# lunchbeats_-_amp.net
KiCad netlist of a schematic drawn in EAGLE
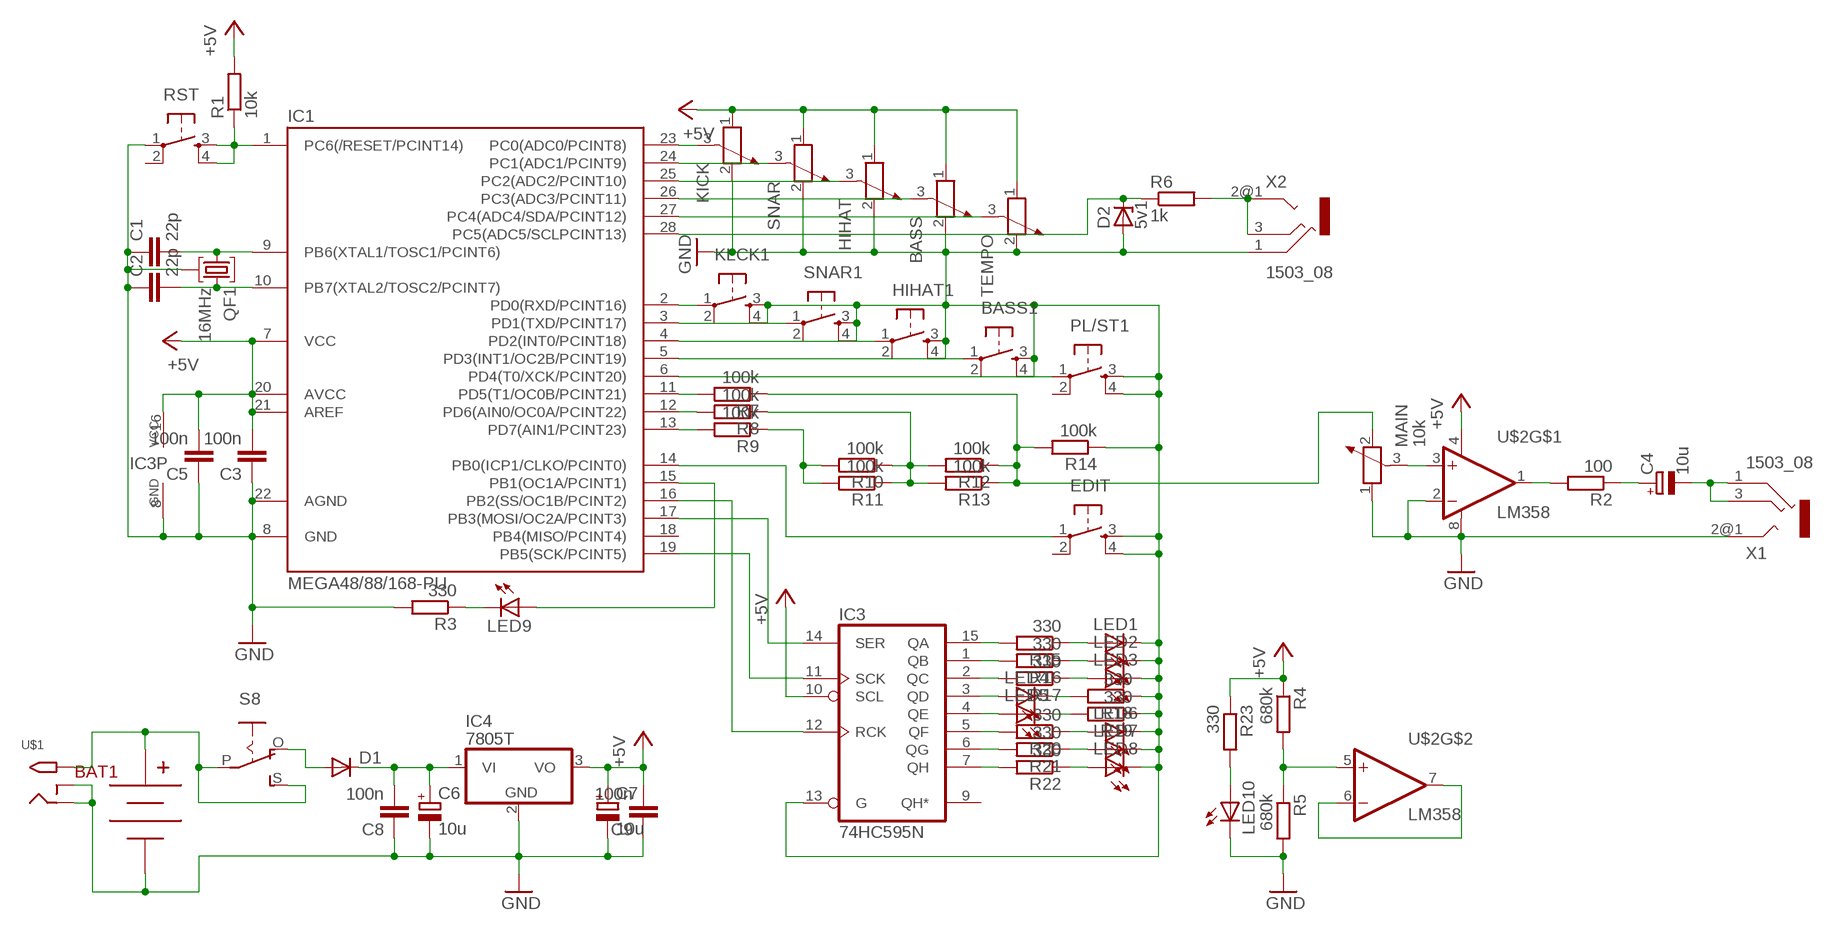
[diagram p0: schematic, sheet 1]

(export (version "E")
  (design (tool "Eeschema 10.0.6"))
  (components
    (comp (ref "BASS")
      (value "POTENTIOMETER_PT-10")
      (footprint "eagle-import:PT-10")
      (libsource (lib "eagle-import") (part "POTENTIOMETER_PT-10"))
    )
    (comp (ref "BASS1")
      (value "TAC_SWITCHPTH")
      (footprint "eagle-import:TACTILE-PTH")
      (libsource (lib "eagle-import") (part "TAC_SWITCHPTH"))
    )
    (comp (ref "BAT1")
      (value "BC9VPC")
      (footprint "eagle-import:BC9VPC")
      (libsource (lib "eagle-import") (part "BC9VPC"))
    )
    (comp (ref "C1")
      (value "22p")
      (footprint "eagle-import:C025-025X050")
      (libsource (lib "eagle-import") (part "C-EU025-025X050"))
    )
    (comp (ref "C2")
      (value "22p")
      (footprint "eagle-import:C025-025X050")
      (libsource (lib "eagle-import") (part "C-EU025-025X050"))
    )
    (comp (ref "C3")
      (value "100n")
      (footprint "eagle-import:C025-025X050")
      (libsource (lib "eagle-import") (part "C-EU025-025X050"))
    )
    (comp (ref "C4")
      (value "10u")
      (footprint "eagle-import:E2,5-6")
      (libsource (lib "eagle-import") (part "CPOL-EUE2.5-6"))
    )
    (comp (ref "C5")
      (value "100n")
      (footprint "eagle-import:C025-025X050")
      (libsource (lib "eagle-import") (part "C-EU025-025X050"))
    )
    (comp (ref "C6")
      (value "10u")
      (footprint "eagle-import:E2,5-5")
      (libsource (lib "eagle-import") (part "CPOL-EUE2.5-5"))
    )
    (comp (ref "C7")
      (value "10u")
      (footprint "eagle-import:E2,5-5")
      (libsource (lib "eagle-import") (part "CPOL-EUE2.5-5"))
    )
    (comp (ref "C8")
      (value "100n")
      (footprint "eagle-import:C025-025X050")
      (libsource (lib "eagle-import") (part "C-EU025-025X050"))
    )
    (comp (ref "C9")
      (value "100n")
      (footprint "eagle-import:C025-025X050")
      (libsource (lib "eagle-import") (part "C-EU025-025X050"))
    )
    (comp (ref "D1")
      (value "DIODE-D-5")
      (footprint "eagle-import:D-5")
      (libsource (lib "eagle-import") (part "DIODE-D-5"))
    )
    (comp (ref "D2")
      (value "5v1")
      (footprint "eagle-import:ZDIO-2.5")
      (libsource (lib "eagle-import") (part "ZENER-DIODEZD-2.5"))
    )
    (comp (ref "EDIT")
      (value "TAC_SWITCHPTH")
      (footprint "eagle-import:TACTILE-PTH")
      (libsource (lib "eagle-import") (part "TAC_SWITCHPTH"))
    )
    (comp (ref "HIHAT")
      (value "POTENTIOMETER_PT-10")
      (footprint "eagle-import:PT-10")
      (libsource (lib "eagle-import") (part "POTENTIOMETER_PT-10"))
    )
    (comp (ref "HIHAT1")
      (value "TAC_SWITCHPTH")
      (footprint "eagle-import:TACTILE-PTH")
      (libsource (lib "eagle-import") (part "TAC_SWITCHPTH"))
    )
    (comp (ref "IC1")
      (value "MEGA48/88/168-PU")
      (footprint "eagle-import:DIL28-3")
      (libsource (lib "eagle-import") (part "MEGA48/88/168-PU"))
    )
    (comp (ref "IC3")
      (value "74HC595N")
      (footprint "eagle-import:DIL16")
      (libsource (lib "eagle-import") (part "74595NHC"))
    )
    (comp (ref "IC4")
      (value "7805T")
      (footprint "eagle-import:TO220H")
      (libsource (lib "eagle-import") (part "78T05"))
    )
    (comp (ref "KICK")
      (value "POTENTIOMETER_PT-10")
      (footprint "eagle-import:PT-10")
      (libsource (lib "eagle-import") (part "POTENTIOMETER_PT-10"))
    )
    (comp (ref "KLCK1")
      (value "TAC_SWITCHPTH")
      (footprint "eagle-import:TACTILE-PTH")
      (libsource (lib "eagle-import") (part "TAC_SWITCHPTH"))
    )
    (comp (ref "LED1")
      (value "LED5MM")
      (footprint "eagle-import:LED5MM")
      (libsource (lib "eagle-import") (part "LED5MM"))
    )
    (comp (ref "LED2")
      (value "LED5MM")
      (footprint "eagle-import:LED5MM")
      (libsource (lib "eagle-import") (part "LED5MM"))
    )
    (comp (ref "LED3")
      (value "LED5MM")
      (footprint "eagle-import:LED5MM")
      (libsource (lib "eagle-import") (part "LED5MM"))
    )
    (comp (ref "LED4")
      (value "LED5MM")
      (footprint "eagle-import:LED5MM")
      (libsource (lib "eagle-import") (part "LED5MM"))
    )
    (comp (ref "LED5")
      (value "LED5MM")
      (footprint "eagle-import:LED5MM")
      (libsource (lib "eagle-import") (part "LED5MM"))
    )
    (comp (ref "LED6")
      (value "LED5MM")
      (footprint "eagle-import:LED5MM")
      (libsource (lib "eagle-import") (part "LED5MM"))
    )
    (comp (ref "LED7")
      (value "LED5MM")
      (footprint "eagle-import:LED5MM")
      (libsource (lib "eagle-import") (part "LED5MM"))
    )
    (comp (ref "LED8")
      (value "LED5MM")
      (footprint "eagle-import:LED5MM")
      (libsource (lib "eagle-import") (part "LED5MM"))
    )
    (comp (ref "LED9")
      (value "LED5MM")
      (footprint "eagle-import:LED5MM")
      (libsource (lib "eagle-import") (part "LED5MM"))
    )
    (comp (ref "LED10")
      (value "LED5MM")
      (footprint "eagle-import:LED5MM")
      (libsource (lib "eagle-import") (part "LED5MM"))
    )
    (comp (ref "MAIN")
      (value "10k")
      (footprint "eagle-import:PT-10")
      (libsource (lib "eagle-import") (part "POTENTIOMETER_PT-10"))
    )
    (comp (ref "PL/ST1")
      (value "TAC_SWITCHPTH")
      (footprint "eagle-import:TACTILE-PTH")
      (libsource (lib "eagle-import") (part "TAC_SWITCHPTH"))
    )
    (comp (ref "QF1")
      (value "16MHz")
      (footprint "eagle-import:HC49U")
      (libsource (lib "eagle-import") (part "8M10AHC49T"))
    )
    (comp (ref "R1")
      (value "10k")
      (footprint "eagle-import:0204_7")
      (libsource (lib "eagle-import") (part "R-EU_0204/7"))
    )
    (comp (ref "R2")
      (value "100")
      (footprint "eagle-import:0204_7")
      (libsource (lib "eagle-import") (part "R-EU_0204/7"))
    )
    (comp (ref "R3")
      (value "330")
      (footprint "eagle-import:0204_7")
      (libsource (lib "eagle-import") (part "R-EU_0204/7"))
    )
    (comp (ref "R4")
      (value "680k")
      (footprint "eagle-import:0204_5")
      (libsource (lib "eagle-import") (part "R-EU_0204/5"))
    )
    (comp (ref "R5")
      (value "680k")
      (footprint "eagle-import:0204_7")
      (libsource (lib "eagle-import") (part "R-EU_0204/7"))
    )
    (comp (ref "R6")
      (value "1k")
      (footprint "eagle-import:0204_7")
      (libsource (lib "eagle-import") (part "R-EU_0204/7"))
    )
    (comp (ref "R7")
      (value "100k")
      (footprint "eagle-import:0204_7")
      (libsource (lib "eagle-import") (part "R-EU_0204/7"))
    )
    (comp (ref "R8")
      (value "100k")
      (footprint "eagle-import:0204_7")
      (libsource (lib "eagle-import") (part "R-EU_0204/7"))
    )
    (comp (ref "R9")
      (value "100k")
      (footprint "eagle-import:0204_7")
      (libsource (lib "eagle-import") (part "R-EU_0204/7"))
    )
    (comp (ref "R10")
      (value "100k")
      (footprint "eagle-import:0204_7")
      (libsource (lib "eagle-import") (part "R-EU_0204/7"))
    )
    (comp (ref "R11")
      (value "100k")
      (footprint "eagle-import:0204_7")
      (libsource (lib "eagle-import") (part "R-EU_0204/7"))
    )
    (comp (ref "R12")
      (value "100k")
      (footprint "eagle-import:0204_7")
      (libsource (lib "eagle-import") (part "R-EU_0204/7"))
    )
    (comp (ref "R13")
      (value "100k")
      (footprint "eagle-import:0204_7")
      (libsource (lib "eagle-import") (part "R-EU_0204/7"))
    )
    (comp (ref "R14")
      (value "100k")
      (footprint "eagle-import:0204_7")
      (libsource (lib "eagle-import") (part "R-EU_0204/7"))
    )
    (comp (ref "R15")
      (value "330")
      (footprint "eagle-import:0204_7")
      (libsource (lib "eagle-import") (part "R-EU_0204/7"))
    )
    (comp (ref "R16")
      (value "330")
      (footprint "eagle-import:0204_7")
      (libsource (lib "eagle-import") (part "R-EU_0204/7"))
    )
    (comp (ref "R17")
      (value "330")
      (footprint "eagle-import:0204_7")
      (libsource (lib "eagle-import") (part "R-EU_0204/7"))
    )
    (comp (ref "R18")
      (value "330")
      (footprint "eagle-import:0204_7")
      (libsource (lib "eagle-import") (part "R-EU_0204/7"))
    )
    (comp (ref "R19")
      (value "330")
      (footprint "eagle-import:0204_7")
      (libsource (lib "eagle-import") (part "R-EU_0204/7"))
    )
    (comp (ref "R20")
      (value "330")
      (footprint "eagle-import:0204_7")
      (libsource (lib "eagle-import") (part "R-EU_0204/7"))
    )
    (comp (ref "R21")
      (value "330")
      (footprint "eagle-import:0204_7")
      (libsource (lib "eagle-import") (part "R-EU_0204/7"))
    )
    (comp (ref "R22")
      (value "330")
      (footprint "eagle-import:0204_7")
      (libsource (lib "eagle-import") (part "R-EU_0204/7"))
    )
    (comp (ref "R23")
      (value "330")
      (footprint "eagle-import:0204_5")
      (libsource (lib "eagle-import") (part "R-EU_0204/5"))
    )
    (comp (ref "RST")
      (value "TAC_SWITCHPTH")
      (footprint "eagle-import:TACTILE-PTH")
      (libsource (lib "eagle-import") (part "TAC_SWITCHPTH"))
    )
    (comp (ref "S8")
      (value "EG1218S")
      (footprint "eagle-import:EG1218")
      (libsource (lib "eagle-import") (part "EG1218S"))
    )
    (comp (ref "SNAR")
      (value "POTENTIOMETER_PT-10")
      (footprint "eagle-import:PT-10")
      (libsource (lib "eagle-import") (part "POTENTIOMETER_PT-10"))
    )
    (comp (ref "SNAR1")
      (value "TAC_SWITCHPTH")
      (footprint "eagle-import:TACTILE-PTH")
      (libsource (lib "eagle-import") (part "TAC_SWITCHPTH"))
    )
    (comp (ref "TEMPO")
      (value "POTENTIOMETER_PT-10")
      (footprint "eagle-import:PT-10")
      (libsource (lib "eagle-import") (part "POTENTIOMETER_PT-10"))
    )
    (comp (ref "U$1")
      (value "2.1MMJACKTHM")
      (footprint "eagle-import:PJ-102A")
      (libsource (lib "eagle-import") (part "2.1MMJACKTHM"))
    )
    (comp (ref "U$2")
      (value "LM358")
      (footprint "eagle-import:DIP08")
      (libsource (lib "eagle-import") (part "LM358"))
    )
    (comp (ref "X1")
      (value "1503_08")
      (footprint "eagle-import:1503_08")
      (libsource (lib "eagle-import") (part "1503_?08"))
    )
    (comp (ref "X2")
      (value "1503_08")
      (footprint "eagle-import:1503_08")
      (fields (field (name "OC_FARNELL") "unknown") (field (name "OC_NEWARK") "unknown"))
      (libsource (lib "eagle-import") (part "1503_?08"))
    )
  )
  (nets
    (net (code "1") (name "+5V") (class "Default")
      (node (ref "BASS") (pin "1") (pinfunction "1_1") (pintype "passive"))
      (node (ref "C3") (pin "2") (pinfunction "2_2") (pintype "passive"))
      (node (ref "C5") (pin "2") (pinfunction "2_2") (pintype "passive"))
      (node (ref "C7") (pin "+") (pinfunction "+_+") (pintype "passive"))
      (node (ref "C9") (pin "2") (pinfunction "2_2") (pintype "passive"))
      (node (ref "HIHAT") (pin "1") (pinfunction "1_1") (pintype "passive"))
      (node (ref "IC1") (pin "20") (pinfunction "AVCC_20") (pintype "passive"))
      (node (ref "IC1") (pin "21") (pinfunction "AREF_21") (pintype "passive"))
      (node (ref "IC1") (pin "7") (pinfunction "VCC_7") (pintype "power_in"))
      (node (ref "IC3") (pin "10") (pinfunction "SCL_10") (pintype "input"))
      (node (ref "IC3") (pin "16") (pinfunction "VCC_16") (pintype "power_in"))
      (node (ref "IC4") (pin "3") (pinfunction "VO_3") (pintype "passive"))
      (node (ref "KICK") (pin "1") (pinfunction "1_1") (pintype "passive"))
      (node (ref "R1") (pin "2") (pinfunction "2_2") (pintype "passive"))
      (node (ref "R23") (pin "1") (pinfunction "1_1") (pintype "passive"))
      (node (ref "R4") (pin "1") (pinfunction "1_1") (pintype "passive"))
      (node (ref "SNAR") (pin "1") (pinfunction "1_1") (pintype "passive"))
      (node (ref "TEMPO") (pin "1") (pinfunction "1_1") (pintype "passive"))
      (node (ref "U$2") (pin "4") (pinfunction "V-_4") (pintype "power_in"))
    )
    (net (code "2") (name "GND") (class "Default")
      (node (ref "BASS") (pin "2") (pinfunction "2_2") (pintype "passive"))
      (node (ref "BASS1") (pin "3") (pinfunction "3_3") (pintype "passive"))
      (node (ref "BASS1") (pin "4") (pinfunction "4_4") (pintype "passive"))
      (node (ref "BAT1") (pin "V-") (pinfunction "V-_V-") (pintype "bidirectional"))
      (node (ref "C1") (pin "1") (pinfunction "1_1") (pintype "passive"))
      (node (ref "C2") (pin "1") (pinfunction "1_1") (pintype "passive"))
      (node (ref "C3") (pin "1") (pinfunction "1_1") (pintype "passive"))
      (node (ref "C5") (pin "1") (pinfunction "1_1") (pintype "passive"))
      (node (ref "C6") (pin "-") (pinfunction "-_-") (pintype "passive"))
      (node (ref "C7") (pin "-") (pinfunction "-_-") (pintype "passive"))
      (node (ref "C8") (pin "1") (pinfunction "1_1") (pintype "passive"))
      (node (ref "C9") (pin "1") (pinfunction "1_1") (pintype "passive"))
      (node (ref "D2") (pin "A") (pinfunction "A_A") (pintype "passive"))
      (node (ref "EDIT") (pin "3") (pinfunction "3_3") (pintype "passive"))
      (node (ref "EDIT") (pin "4") (pinfunction "4_4") (pintype "passive"))
      (node (ref "HIHAT") (pin "2") (pinfunction "2_2") (pintype "passive"))
      (node (ref "HIHAT1") (pin "3") (pinfunction "3_3") (pintype "passive"))
      (node (ref "HIHAT1") (pin "4") (pinfunction "4_4") (pintype "passive"))
      (node (ref "IC1") (pin "22") (pinfunction "AGND_22") (pintype "power_in"))
      (node (ref "IC1") (pin "8") (pinfunction "GND_8") (pintype "power_in"))
      (node (ref "IC3") (pin "13") (pinfunction "G_13") (pintype "input"))
      (node (ref "IC3") (pin "8") (pinfunction "GND_8") (pintype "power_in"))
      (node (ref "IC4") (pin "2") (pinfunction "GND_2") (pintype "passive"))
      (node (ref "KICK") (pin "2") (pinfunction "2_2") (pintype "passive"))
      (node (ref "KLCK1") (pin "3") (pinfunction "3_3") (pintype "passive"))
      (node (ref "KLCK1") (pin "4") (pinfunction "4_4") (pintype "passive"))
      (node (ref "LED1") (pin "K") (pinfunction "C_K") (pintype "passive"))
      (node (ref "LED10") (pin "K") (pinfunction "C_K") (pintype "passive"))
      (node (ref "LED2") (pin "K") (pinfunction "C_K") (pintype "passive"))
      (node (ref "LED3") (pin "K") (pinfunction "C_K") (pintype "passive"))
      (node (ref "LED6") (pin "K") (pinfunction "C_K") (pintype "passive"))
      (node (ref "LED7") (pin "K") (pinfunction "C_K") (pintype "passive"))
      (node (ref "LED8") (pin "K") (pinfunction "C_K") (pintype "passive"))
      (node (ref "MAIN") (pin "1") (pinfunction "1_1") (pintype "passive"))
      (node (ref "PL/ST1") (pin "3") (pinfunction "3_3") (pintype "passive"))
      (node (ref "PL/ST1") (pin "4") (pinfunction "4_4") (pintype "passive"))
      (node (ref "QF1") (pin "2") (pinfunction "2_2") (pintype "passive"))
      (node (ref "R14") (pin "1") (pinfunction "1_1") (pintype "passive"))
      (node (ref "R18") (pin "1") (pinfunction "1_1") (pintype "passive"))
      (node (ref "R19") (pin "1") (pinfunction "1_1") (pintype "passive"))
      (node (ref "R3") (pin "2") (pinfunction "2_2") (pintype "passive"))
      (node (ref "R5") (pin "2") (pinfunction "2_2") (pintype "passive"))
      (node (ref "RST") (pin "1") (pinfunction "1_1") (pintype "passive"))
      (node (ref "SNAR") (pin "2") (pinfunction "2_2") (pintype "passive"))
      (node (ref "SNAR1") (pin "3") (pinfunction "3_3") (pintype "passive"))
      (node (ref "SNAR1") (pin "4") (pinfunction "4_4") (pintype "passive"))
      (node (ref "TEMPO") (pin "2") (pinfunction "2_2") (pintype "passive"))
      (node (ref "U$1") (pin "RING") (pinfunction "RING_RING") (pintype "bidirectional"))
      (node (ref "U$1") (pin "RING_SW") (pinfunction "RING_SW_RING_SW") (pintype "bidirectional"))
      (node (ref "U$2") (pin "2") (pinfunction "-IN_2") (pintype "input"))
      (node (ref "U$2") (pin "8") (pinfunction "V+_8") (pintype "power_in"))
      (node (ref "X1") (pin "2@1") (pinfunction "2_2@1") (pintype "passive"))
      (node (ref "X2") (pin "1") (pinfunction "1_1") (pintype "passive"))
    )
    (net (code "3") (name "Net-(BAT1-PadV+)") (class "Default")
      (node (ref "BAT1") (pin "V+") (pinfunction "V+_V+") (pintype "bidirectional"))
      (node (ref "S8") (pin "P") (pinfunction "P_P") (pintype "passive"))
      (node (ref "S8") (pin "S") (pinfunction "S_S") (pintype "passive"))
      (node (ref "U$1") (pin "TIP") (pinfunction "TIP_TIP") (pintype "bidirectional"))
    )
    (net (code "4") (name "Net-(C4-Pad+)") (class "Default")
      (node (ref "C4") (pin "+") (pinfunction "+_+") (pintype "passive"))
      (node (ref "R2") (pin "1") (pinfunction "1_1") (pintype "passive"))
    )
    (net (code "5") (name "Net-(C4-Pad-)") (class "Default")
      (node (ref "C4") (pin "-") (pinfunction "-_-") (pintype "passive"))
      (node (ref "X1") (pin "1") (pinfunction "1_1") (pintype "passive"))
      (node (ref "X1") (pin "3") (pinfunction "3_3") (pintype "passive"))
    )
    (net (code "6") (name "Net-(D1-PadA)") (class "Default")
      (node (ref "D1") (pin "A") (pinfunction "A_A") (pintype "passive"))
      (node (ref "S8") (pin "O") (pinfunction "O_O") (pintype "passive"))
    )
    (net (code "7") (name "Net-(IC1-PB0(ICP1{slash}CLKO{slash}PCINT0))") (class "Default")
      (node (ref "EDIT") (pin "1") (pinfunction "1_1") (pintype "passive"))
      (node (ref "IC1") (pin "14") (pinfunction "PB0(ICP1/CLKO/PCINT0)_14") (pintype "bidirectional"))
    )
    (net (code "8") (name "Net-(IC1-PB1(OC1A{slash}PCINT1))") (class "Default")
      (node (ref "IC1") (pin "15") (pinfunction "PB1(OC1A/PCINT1)_15") (pintype "bidirectional"))
      (node (ref "LED9") (pin "A") (pinfunction "A_A") (pintype "passive"))
    )
    (net (code "9") (name "Net-(IC1-PB2(SS{slash}OC1B{slash}PCINT2))") (class "Default")
      (node (ref "IC1") (pin "16") (pinfunction "PB2(SS/OC1B/PCINT2)_16") (pintype "bidirectional"))
      (node (ref "IC3") (pin "12") (pinfunction "RCK_12") (pintype "input"))
    )
    (net (code "10") (name "Net-(IC1-PB3(MOSI{slash}OC2A{slash}PCINT3))") (class "Default")
      (node (ref "IC1") (pin "17") (pinfunction "PB3(MOSI/OC2A/PCINT3)_17") (pintype "bidirectional"))
      (node (ref "IC3") (pin "14") (pinfunction "SER_14") (pintype "input"))
    )
    (net (code "11") (name "Net-(IC1-PB5(SCK{slash}PCINT5))") (class "Default")
      (node (ref "IC1") (pin "19") (pinfunction "PB5(SCK/PCINT5)_19") (pintype "bidirectional"))
      (node (ref "IC3") (pin "11") (pinfunction "SCK_11") (pintype "input"))
    )
    (net (code "12") (name "Net-(IC1-PB6(XTAL1{slash}TOSC1{slash}PCINT6))") (class "Default")
      (node (ref "C1") (pin "2") (pinfunction "2_2") (pintype "passive"))
      (node (ref "IC1") (pin "9") (pinfunction "PB6(XTAL1/TOSC1/PCINT6)_9") (pintype "bidirectional"))
      (node (ref "QF1") (pin "1") (pinfunction "1_1") (pintype "passive"))
    )
    (net (code "13") (name "Net-(IC1-PB7(XTAL2{slash}TOSC2{slash}PCINT7))") (class "Default")
      (node (ref "C2") (pin "2") (pinfunction "2_2") (pintype "passive"))
      (node (ref "IC1") (pin "10") (pinfunction "PB7(XTAL2/TOSC2/PCINT7)_10") (pintype "bidirectional"))
      (node (ref "QF1") (pin "3") (pinfunction "3_3") (pintype "passive"))
    )
    (net (code "14") (name "Net-(IC1-PC0(ADC0{slash}PCINT8))") (class "Default")
      (node (ref "IC1") (pin "23") (pinfunction "PC0(ADC0/PCINT8)_23") (pintype "bidirectional"))
      (node (ref "KICK") (pin "3") (pinfunction "3_3") (pintype "passive"))
    )
    (net (code "15") (name "Net-(IC1-PC1(ADC1{slash}PCINT9))") (class "Default")
      (node (ref "IC1") (pin "24") (pinfunction "PC1(ADC1/PCINT9)_24") (pintype "bidirectional"))
      (node (ref "SNAR") (pin "3") (pinfunction "3_3") (pintype "passive"))
    )
    (net (code "16") (name "Net-(IC1-PC2(ADC2{slash}PCINT10))") (class "Default")
      (node (ref "HIHAT") (pin "3") (pinfunction "3_3") (pintype "passive"))
      (node (ref "IC1") (pin "25") (pinfunction "PC2(ADC2/PCINT10)_25") (pintype "bidirectional"))
    )
    (net (code "17") (name "Net-(IC1-PC3(ADC3{slash}PCINT11))") (class "Default")
      (node (ref "BASS") (pin "3") (pinfunction "3_3") (pintype "passive"))
      (node (ref "IC1") (pin "26") (pinfunction "PC3(ADC3/PCINT11)_26") (pintype "bidirectional"))
    )
    (net (code "18") (name "Net-(IC1-PC4(ADC4{slash}SDA{slash}PCINT12))") (class "Default")
      (node (ref "IC1") (pin "27") (pinfunction "PC4(ADC4/SDA/PCINT12)_27") (pintype "bidirectional"))
      (node (ref "TEMPO") (pin "3") (pinfunction "3_3") (pintype "passive"))
    )
    (net (code "19") (name "Net-(IC1-PC5(ADC5{slash}SCLPCINT13))") (class "Default")
      (node (ref "D2") (pin "C") (pinfunction "C_C") (pintype "passive"))
      (node (ref "IC1") (pin "28") (pinfunction "PC5(ADC5/SCLPCINT13)_28") (pintype "bidirectional"))
      (node (ref "R6") (pin "1") (pinfunction "1_1") (pintype "passive"))
    )
    (net (code "20") (name "Net-(IC1-PC6({slash}RESET{slash}PCINT14))") (class "Default")
      (node (ref "IC1") (pin "1") (pinfunction "PC6(/RESET/PCINT14)_1") (pintype "bidirectional"))
      (node (ref "R1") (pin "1") (pinfunction "1_1") (pintype "passive"))
      (node (ref "RST") (pin "3") (pinfunction "3_3") (pintype "passive"))
      (node (ref "RST") (pin "4") (pinfunction "4_4") (pintype "passive"))
    )
    (net (code "21") (name "Net-(IC1-PD0(RXD{slash}PCINT16))") (class "Default")
      (node (ref "IC1") (pin "2") (pinfunction "PD0(RXD/PCINT16)_2") (pintype "bidirectional"))
      (node (ref "KLCK1") (pin "1") (pinfunction "1_1") (pintype "passive"))
    )
    (net (code "22") (name "Net-(IC1-PD1(TXD{slash}PCINT17))") (class "Default")
      (node (ref "IC1") (pin "3") (pinfunction "PD1(TXD/PCINT17)_3") (pintype "bidirectional"))
      (node (ref "SNAR1") (pin "1") (pinfunction "1_1") (pintype "passive"))
    )
    (net (code "23") (name "Net-(IC1-PD2(INT0{slash}PCINT18))") (class "Default")
      (node (ref "HIHAT1") (pin "1") (pinfunction "1_1") (pintype "passive"))
      (node (ref "IC1") (pin "4") (pinfunction "PD2(INT0/PCINT18)_4") (pintype "bidirectional"))
    )
    (net (code "24") (name "Net-(IC1-PD3(INT1{slash}OC2B{slash}PCINT19))") (class "Default")
      (node (ref "BASS1") (pin "1") (pinfunction "1_1") (pintype "passive"))
      (node (ref "IC1") (pin "5") (pinfunction "PD3(INT1/OC2B/PCINT19)_5") (pintype "bidirectional"))
    )
    (net (code "25") (name "Net-(IC1-PD4(T0{slash}XCK{slash}PCINT20))") (class "Default")
      (node (ref "IC1") (pin "6") (pinfunction "PD4(T0/XCK/PCINT20)_6") (pintype "bidirectional"))
      (node (ref "PL/ST1") (pin "1") (pinfunction "1_1") (pintype "passive"))
    )
    (net (code "26") (name "Net-(IC1-PD5(T1{slash}OC0B{slash}PCINT21))") (class "Default")
      (node (ref "IC1") (pin "11") (pinfunction "PD5(T1/OC0B/PCINT21)_11") (pintype "bidirectional"))
      (node (ref "R7") (pin "2") (pinfunction "2_2") (pintype "passive"))
    )
    (net (code "27") (name "Net-(IC1-PD6(AIN0{slash}OC0A{slash}PCINT22))") (class "Default")
      (node (ref "IC1") (pin "12") (pinfunction "PD6(AIN0/OC0A/PCINT22)_12") (pintype "bidirectional"))
      (node (ref "R8") (pin "2") (pinfunction "2_2") (pintype "passive"))
    )
    (net (code "28") (name "Net-(IC1-PD7(AIN1{slash}PCINT23))") (class "Default")
      (node (ref "IC1") (pin "13") (pinfunction "PD7(AIN1/PCINT23)_13") (pintype "bidirectional"))
      (node (ref "R9") (pin "2") (pinfunction "2_2") (pintype "passive"))
    )
    (net (code "29") (name "Net-(IC3A-QA)") (class "Default")
      (node (ref "IC3") (pin "15") (pinfunction "QA_15") (pintype "tri_state"))
      (node (ref "R15") (pin "2") (pinfunction "2_2") (pintype "passive"))
    )
    (net (code "30") (name "Net-(IC3A-QB)") (class "Default")
      (node (ref "IC3") (pin "1") (pinfunction "QB_1") (pintype "tri_state"))
      (node (ref "R16") (pin "2") (pinfunction "2_2") (pintype "passive"))
    )
    (net (code "31") (name "Net-(IC3A-QC)") (class "Default")
      (node (ref "IC3") (pin "2") (pinfunction "QC_2") (pintype "tri_state"))
      (node (ref "R17") (pin "2") (pinfunction "2_2") (pintype "passive"))
    )
    (net (code "32") (name "Net-(IC3A-QD)") (class "Default")
      (node (ref "IC3") (pin "3") (pinfunction "QD_3") (pintype "tri_state"))
      (node (ref "LED4") (pin "A") (pinfunction "A_A") (pintype "passive"))
    )
    (net (code "33") (name "Net-(IC3A-QE)") (class "Default")
      (node (ref "IC3") (pin "4") (pinfunction "QE_4") (pintype "tri_state"))
      (node (ref "LED5") (pin "A") (pinfunction "A_A") (pintype "passive"))
    )
    (net (code "34") (name "Net-(IC3A-QF)") (class "Default")
      (node (ref "IC3") (pin "5") (pinfunction "QF_5") (pintype "tri_state"))
      (node (ref "R20") (pin "2") (pinfunction "2_2") (pintype "passive"))
    )
    (net (code "35") (name "Net-(IC3A-QG)") (class "Default")
      (node (ref "IC3") (pin "6") (pinfunction "QG_6") (pintype "tri_state"))
      (node (ref "R21") (pin "2") (pinfunction "2_2") (pintype "passive"))
    )
    (net (code "36") (name "Net-(IC3A-QH)") (class "Default")
      (node (ref "IC3") (pin "7") (pinfunction "QH_7") (pintype "tri_state"))
      (node (ref "R22") (pin "2") (pinfunction "2_2") (pintype "passive"))
    )
    (net (code "37") (name "Net-(IC4-VI)") (class "Default")
      (node (ref "C6") (pin "+") (pinfunction "+_+") (pintype "passive"))
      (node (ref "C8") (pin "2") (pinfunction "2_2") (pintype "passive"))
      (node (ref "D1") (pin "C") (pinfunction "C_C") (pintype "passive"))
      (node (ref "IC4") (pin "1") (pinfunction "VI_1") (pintype "input"))
    )
    (net (code "38") (name "Net-(LED1-PadA)") (class "Default")
      (node (ref "LED1") (pin "A") (pinfunction "A_A") (pintype "passive"))
      (node (ref "R15") (pin "1") (pinfunction "1_1") (pintype "passive"))
    )
    (net (code "39") (name "Net-(LED2-PadA)") (class "Default")
      (node (ref "LED2") (pin "A") (pinfunction "A_A") (pintype "passive"))
      (node (ref "R16") (pin "1") (pinfunction "1_1") (pintype "passive"))
    )
    (net (code "40") (name "Net-(LED3-PadA)") (class "Default")
      (node (ref "LED3") (pin "A") (pinfunction "A_A") (pintype "passive"))
      (node (ref "R17") (pin "1") (pinfunction "1_1") (pintype "passive"))
    )
    (net (code "41") (name "Net-(LED4-C)") (class "Default")
      (node (ref "LED4") (pin "K") (pinfunction "C_K") (pintype "passive"))
      (node (ref "R18") (pin "2") (pinfunction "2_2") (pintype "passive"))
    )
    (net (code "42") (name "Net-(LED5-C)") (class "Default")
      (node (ref "LED5") (pin "K") (pinfunction "C_K") (pintype "passive"))
      (node (ref "R19") (pin "2") (pinfunction "2_2") (pintype "passive"))
    )
    (net (code "43") (name "Net-(LED6-PadA)") (class "Default")
      (node (ref "LED6") (pin "A") (pinfunction "A_A") (pintype "passive"))
      (node (ref "R20") (pin "1") (pinfunction "1_1") (pintype "passive"))
    )
    (net (code "44") (name "Net-(LED7-PadA)") (class "Default")
      (node (ref "LED7") (pin "A") (pinfunction "A_A") (pintype "passive"))
      (node (ref "R21") (pin "1") (pinfunction "1_1") (pintype "passive"))
    )
    (net (code "45") (name "Net-(LED8-PadA)") (class "Default")
      (node (ref "LED8") (pin "A") (pinfunction "A_A") (pintype "passive"))
      (node (ref "R22") (pin "1") (pinfunction "1_1") (pintype "passive"))
    )
    (net (code "46") (name "Net-(LED9-C)") (class "Default")
      (node (ref "LED9") (pin "K") (pinfunction "C_K") (pintype "passive"))
      (node (ref "R3") (pin "1") (pinfunction "1_1") (pintype "passive"))
    )
    (net (code "47") (name "Net-(LED10-PadA)") (class "Default")
      (node (ref "LED10") (pin "A") (pinfunction "A_A") (pintype "passive"))
      (node (ref "R23") (pin "2") (pinfunction "2_2") (pintype "passive"))
    )
    (net (code "48") (name "Net-(MAIN-Pad2)") (class "Default")
      (node (ref "MAIN") (pin "2") (pinfunction "2_2") (pintype "passive"))
      (node (ref "R12") (pin "1") (pinfunction "1_1") (pintype "passive"))
      (node (ref "R13") (pin "1") (pinfunction "1_1") (pintype "passive"))
      (node (ref "R14") (pin "2") (pinfunction "2_2") (pintype "passive"))
      (node (ref "R7") (pin "1") (pinfunction "1_1") (pintype "passive"))
    )
    (net (code "49") (name "Net-(R6-Pad2)") (class "Default")
      (node (ref "R6") (pin "2") (pinfunction "2_2") (pintype "passive"))
      (node (ref "X2") (pin "2@1") (pinfunction "2_2@1") (pintype "passive"))
      (node (ref "X2") (pin "3") (pinfunction "3_3") (pintype "passive"))
    )
    (net (code "50") (name "Net-(R10-Pad1)") (class "Default")
      (node (ref "R10") (pin "1") (pinfunction "1_1") (pintype "passive"))
      (node (ref "R11") (pin "1") (pinfunction "1_1") (pintype "passive"))
      (node (ref "R12") (pin "2") (pinfunction "2_2") (pintype "passive"))
      (node (ref "R13") (pin "2") (pinfunction "2_2") (pintype "passive"))
      (node (ref "R8") (pin "1") (pinfunction "1_1") (pintype "passive"))
    )
    (net (code "51") (name "Net-(R10-Pad2)") (class "Default")
      (node (ref "R10") (pin "2") (pinfunction "2_2") (pintype "passive"))
      (node (ref "R11") (pin "2") (pinfunction "2_2") (pintype "passive"))
      (node (ref "R9") (pin "1") (pinfunction "1_1") (pintype "passive"))
    )
    (net (code "52") (name "Net-(U$2A-+IN)") (class "Default")
      (node (ref "MAIN") (pin "3") (pinfunction "3_3") (pintype "passive"))
      (node (ref "U$2") (pin "3") (pinfunction "+IN_3") (pintype "input"))
    )
    (net (code "53") (name "Net-(U$2A-OUT)") (class "Default")
      (node (ref "R2") (pin "2") (pinfunction "2_2") (pintype "passive"))
      (node (ref "U$2") (pin "1") (pinfunction "OUT_1") (pintype "output"))
    )
    (net (code "54") (name "Net-(U$2B-+IN)") (class "Default")
      (node (ref "R4") (pin "2") (pinfunction "2_2") (pintype "passive"))
      (node (ref "R5") (pin "1") (pinfunction "1_1") (pintype "passive"))
      (node (ref "U$2") (pin "5") (pinfunction "+IN_5") (pintype "input"))
    )
    (net (code "55") (name "Net-(U$2B--IN)") (class "Default")
      (node (ref "U$2") (pin "6") (pinfunction "-IN_6") (pintype "input"))
      (node (ref "U$2") (pin "7") (pinfunction "OUT_7") (pintype "output"))
    )
    (net (code "56") (name "unconnected-(BASS1-Pad2)") (class "Default")
      (node (ref "BASS1") (pin "2") (pinfunction "2_2") (pintype "passive"))
    )
    (net (code "57") (name "unconnected-(EDIT-Pad2)") (class "Default")
      (node (ref "EDIT") (pin "2") (pinfunction "2_2") (pintype "passive"))
    )
    (net (code "58") (name "unconnected-(HIHAT1-Pad2)") (class "Default")
      (node (ref "HIHAT1") (pin "2") (pinfunction "2_2") (pintype "passive"))
    )
    (net (code "59") (name "unconnected-(IC1-PB4(MISO{slash}PCINT4)-Pad18)") (class "Default")
      (node (ref "IC1") (pin "18") (pinfunction "PB4(MISO/PCINT4)_18") (pintype "bidirectional"))
    )
    (net (code "60") (name "unconnected-(IC3A-QH*-Pad9)") (class "Default")
      (node (ref "IC3") (pin "9") (pinfunction "QH*_9") (pintype "tri_state"))
    )
    (net (code "61") (name "unconnected-(KLCK1-Pad2)") (class "Default")
      (node (ref "KLCK1") (pin "2") (pinfunction "2_2") (pintype "passive"))
    )
    (net (code "62") (name "unconnected-(PL/ST1-Pad2)") (class "Default")
      (node (ref "PL/ST1") (pin "2") (pinfunction "2_2") (pintype "passive"))
    )
    (net (code "63") (name "unconnected-(RST-Pad2)") (class "Default")
      (node (ref "RST") (pin "2") (pinfunction "2_2") (pintype "passive"))
    )
    (net (code "64") (name "unconnected-(SNAR1-Pad2)") (class "Default")
      (node (ref "SNAR1") (pin "2") (pinfunction "2_2") (pintype "passive"))
    )
    (net (code "65") (name "unconnected-(X1-2-Pad2@2)") (class "Default")
      (node (ref "X1") (pin "2@2") (pinfunction "2_2@2") (pintype "passive"))
    )
    (net (code "66") (name "unconnected-(X2-2-Pad2@2)") (class "Default")
      (node (ref "X2") (pin "2@2") (pinfunction "2_2@2") (pintype "passive"))
    )
  )
)
